# interfaceBoard.net
KiCad netlist of a schematic drawn in EAGLE
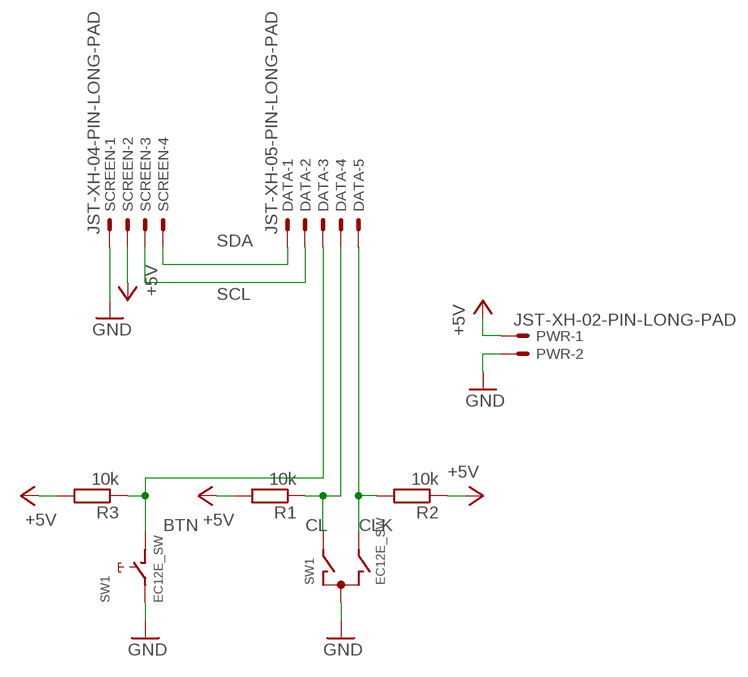
[diagram p0: schematic, sheet 1]

(export (version "E")
  (design (tool "Eeschema 10.0.6"))
  (components
    (comp (ref "DATA")
      (value "JST-XH-05-PIN-LONG-PAD")
      (footprint "eagle-import:JST-XH-05-PACKAGE-LONG-PAD")
      (libsource (lib "eagle-import") (part "JST-XH-05-PIN-LONG-PAD"))
    )
    (comp (ref "PWR")
      (value "JST-XH-02-PIN-LONG-PAD")
      (footprint "eagle-import:JST-XH-02-PACKAGE-LONG-PAD")
      (libsource (lib "eagle-import") (part "JST-XH-02-PIN-LONG-PAD"))
    )
    (comp (ref "R1")
      (value "10k")
      (footprint "eagle-import:0204_7")
      (libsource (lib "eagle-import") (part "R-EU_0204/7"))
    )
    (comp (ref "R2")
      (value "10k")
      (footprint "eagle-import:0204_7")
      (libsource (lib "eagle-import") (part "R-EU_0204/7"))
    )
    (comp (ref "R3")
      (value "10k")
      (footprint "eagle-import:0204_7")
      (libsource (lib "eagle-import") (part "R-EU_0204/7"))
    )
    (comp (ref "SCREEN")
      (value "JST-XH-04-PIN-LONG-PAD")
      (footprint "eagle-import:JST-XH-04-PACKAGE-LONG-PAD")
      (libsource (lib "eagle-import") (part "JST-XH-04-PIN-LONG-PAD"))
    )
    (comp (ref "SW1")
      (value "EC12E_SW")
      (footprint "eagle-import:ALPS_EC12E_SW")
      (fields (field (name "MPN") "EC12E2424407"))
      (libsource (lib "eagle-import") (part "EC12E_SW"))
    )
  )
  (nets
    (net (code "1") (name "+5V") (class "Default")
      (node (ref "PWR") (pin "1") (pinfunction "S_1") (pintype "passive"))
      (node (ref "R1") (pin "2") (pinfunction "2_2") (pintype "passive"))
      (node (ref "R2") (pin "1") (pinfunction "1_1") (pintype "passive"))
      (node (ref "R3") (pin "2") (pinfunction "2_2") (pintype "passive"))
      (node (ref "SCREEN") (pin "2") (pinfunction "S_2") (pintype "passive"))
    )
    (net (code "2") (name "/BTN") (class "Default")
      (node (ref "DATA") (pin "3") (pinfunction "S_3") (pintype "passive"))
      (node (ref "R3") (pin "1") (pinfunction "1_1") (pintype "passive"))
      (node (ref "SW1") (pin "D") (pinfunction "1_D") (pintype "passive"))
    )
    (net (code "3") (name "/CL") (class "Default")
      (node (ref "DATA") (pin "4") (pinfunction "S_4") (pintype "passive"))
      (node (ref "R1") (pin "1") (pinfunction "1_1") (pintype "passive"))
      (node (ref "SW1") (pin "A") (pinfunction "A_A") (pintype "passive"))
    )
    (net (code "4") (name "/CLK") (class "Default")
      (node (ref "DATA") (pin "5") (pinfunction "S_5") (pintype "passive"))
      (node (ref "R2") (pin "2") (pinfunction "2_2") (pintype "passive"))
      (node (ref "SW1") (pin "B") (pinfunction "B_B") (pintype "passive"))
    )
    (net (code "5") (name "/SCL") (class "Default")
      (node (ref "DATA") (pin "2") (pinfunction "S_2") (pintype "passive"))
      (node (ref "SCREEN") (pin "3") (pinfunction "S_3") (pintype "passive"))
    )
    (net (code "6") (name "/SDA") (class "Default")
      (node (ref "DATA") (pin "1") (pinfunction "S_1") (pintype "passive"))
      (node (ref "SCREEN") (pin "4") (pinfunction "S_4") (pintype "passive"))
    )
    (net (code "7") (name "GND") (class "Default")
      (node (ref "PWR") (pin "2") (pinfunction "S_2") (pintype "passive"))
      (node (ref "SCREEN") (pin "1") (pinfunction "S_1") (pintype "passive"))
      (node (ref "SW1") (pin "C") (pinfunction "C_C") (pintype "passive"))
      (node (ref "SW1") (pin "E") (pinfunction "2_E") (pintype "passive"))
    )
  )
)
